# working.net
KiCad netlist of a schematic drawn in EAGLE
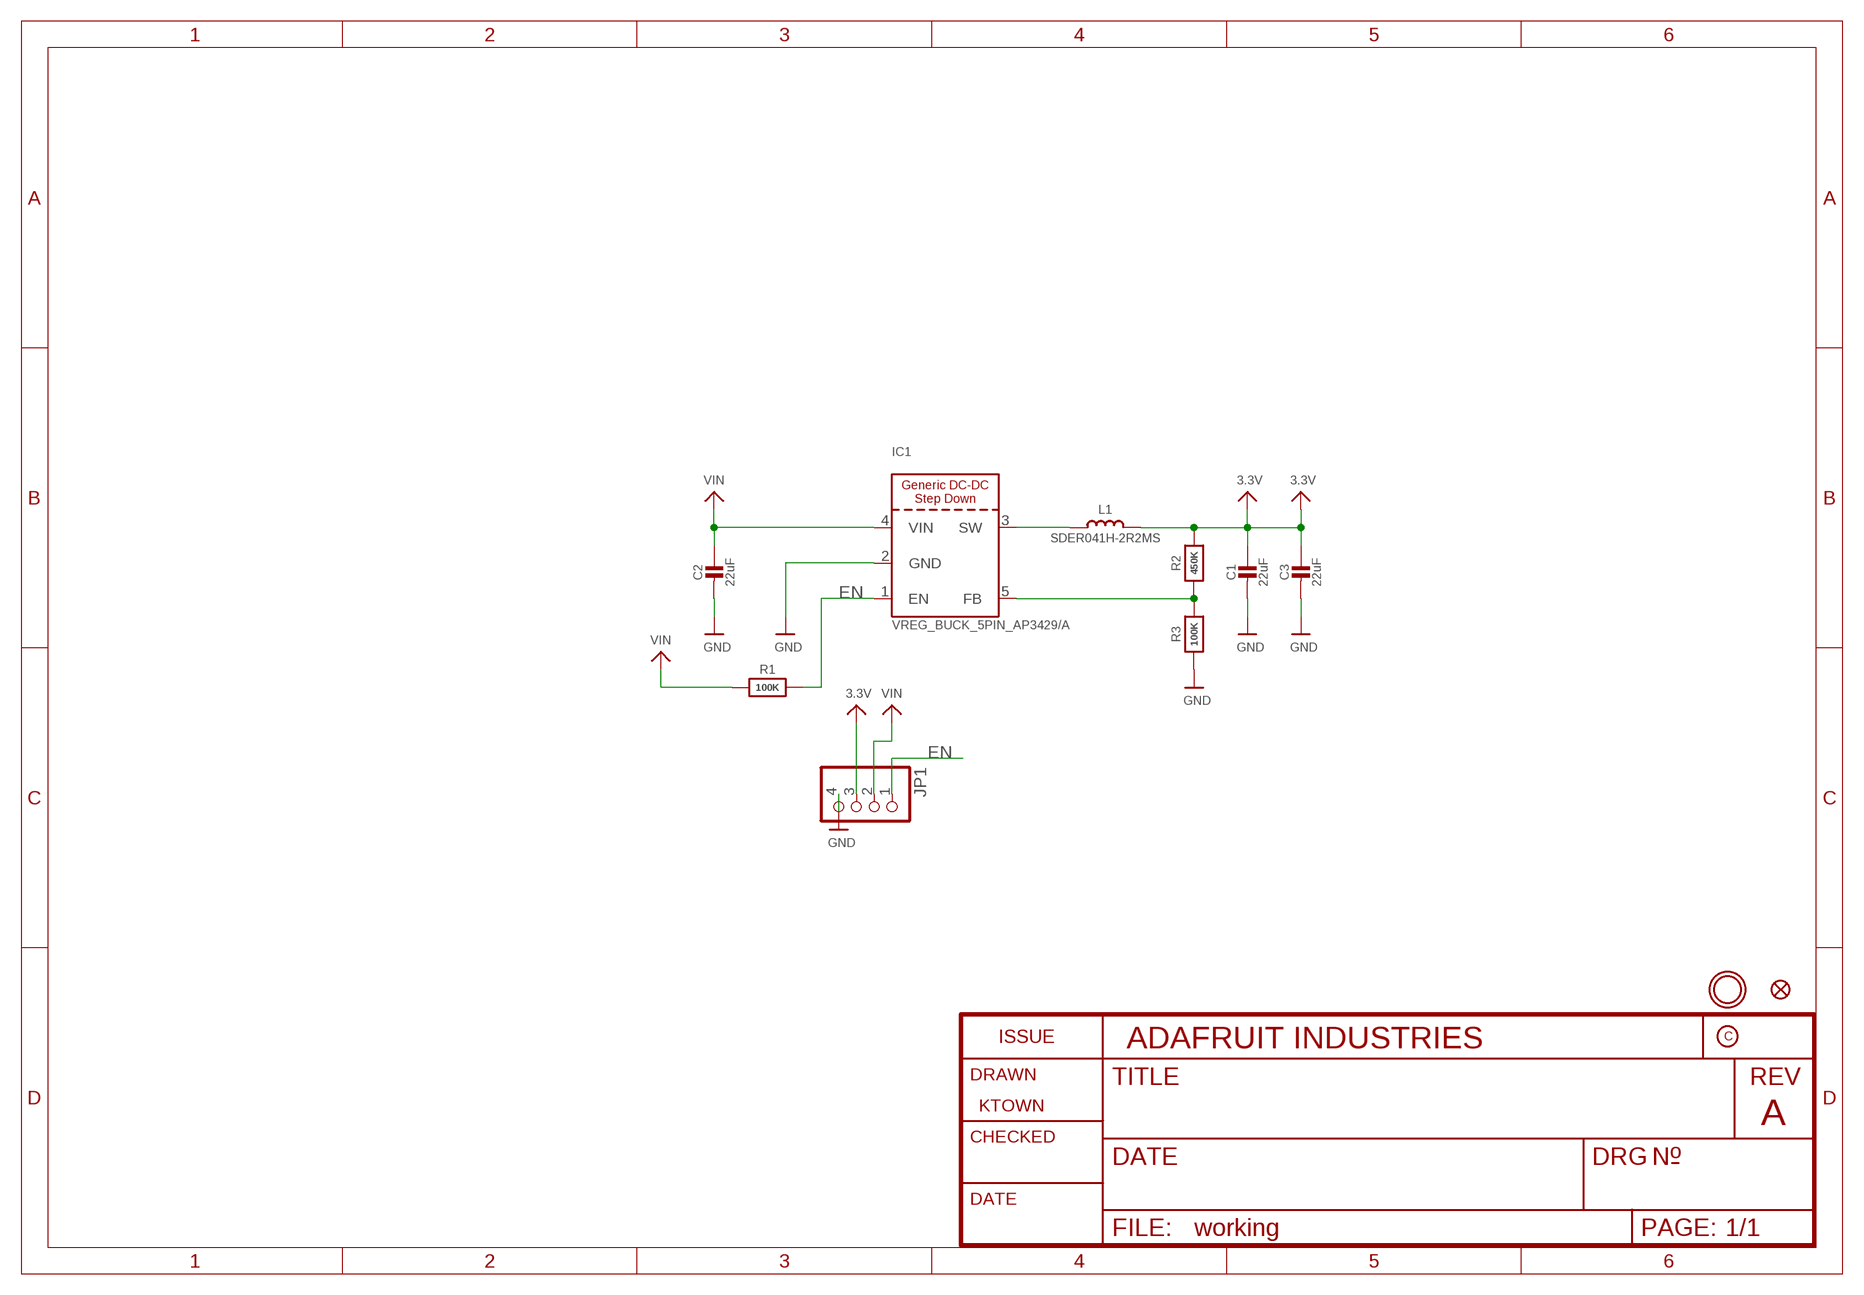
[diagram p0: schematic, sheet 1]

(export (version "E")
  (design (tool "Eeschema 10.0.6"))
  (components
    (comp (ref "C1")
      (value "22uF")
      (footprint "eagle-import:0805-NO")
      (libsource (lib "eagle-import") (part "CAP_CERAMIC0805-NOOUTLINE"))
    )
    (comp (ref "C2")
      (value "22uF")
      (footprint "eagle-import:0805-NO")
      (libsource (lib "eagle-import") (part "CAP_CERAMIC0805-NOOUTLINE"))
    )
    (comp (ref "C3")
      (value "22uF")
      (footprint "eagle-import:0805-NO")
      (libsource (lib "eagle-import") (part "CAP_CERAMIC0805-NOOUTLINE"))
    )
    (comp (ref "FID1")
      (value "FIDUCIAL_1MM")
      (footprint "eagle-import:FIDUCIAL_1MM")
      (libsource (lib "eagle-import") (part "FIDUCIAL_1MM"))
    )
    (comp (ref "IC1")
      (value "VREG_BUCK_5PIN_AP3429/A")
      (footprint "eagle-import:SOT23-5")
      (libsource (lib "eagle-import") (part "VREG_BUCK_5PIN_AP3429/A"))
    )
    (comp (ref "JP1")
      (value "HEADER-1X4ROUND")
      (footprint "eagle-import:1X04_ROUND")
      (libsource (lib "eagle-import") (part "HEADER-1X4ROUND"))
    )
    (comp (ref "L1")
      (value "SDER041H-2R2MS")
      (footprint "eagle-import:INDUCTOR_TAIYOYUDEN_NRH2412T")
      (libsource (lib "eagle-import") (part "INDUCTORNRH2412T"))
    )
    (comp (ref "R1")
      (value "100K")
      (footprint "eagle-import:0603-NO")
      (libsource (lib "eagle-import") (part "RESISTOR_0603_NOOUT"))
    )
    (comp (ref "R2")
      (value "450K")
      (footprint "eagle-import:0603-NO")
      (libsource (lib "eagle-import") (part "RESISTOR_0603_NOOUT"))
    )
    (comp (ref "R3")
      (value "100K")
      (footprint "eagle-import:0603-NO")
      (libsource (lib "eagle-import") (part "RESISTOR_0603_NOOUT"))
    )
    (comp (ref "U$9")
      (value "MOUNTINGHOLE2.5")
      (footprint "eagle-import:MOUNTINGHOLE_2.5_PLATED")
      (libsource (lib "eagle-import") (part "MOUNTINGHOLE2.5"))
    )
  )
  (nets
    (net (code "1") (name "/EN") (class "Default")
      (node (ref "IC1") (pin "1") (pinfunction "EN_1") (pintype "input"))
      (node (ref "JP1") (pin "1") (pinfunction "1_1") (pintype "passive"))
      (node (ref "R1") (pin "2") (pinfunction "2_2") (pintype "passive"))
    )
    (net (code "2") (name "3.3V") (class "Default")
      (node (ref "C1") (pin "1") (pinfunction "1_1") (pintype "passive"))
      (node (ref "C3") (pin "1") (pinfunction "1_1") (pintype "passive"))
      (node (ref "JP1") (pin "3") (pinfunction "3_3") (pintype "passive"))
      (node (ref "L1") (pin "2") (pinfunction "2_2") (pintype "passive"))
      (node (ref "R2") (pin "2") (pinfunction "2_2") (pintype "passive"))
    )
    (net (code "3") (name "GND") (class "Default")
      (node (ref "C1") (pin "2") (pinfunction "2_2") (pintype "passive"))
      (node (ref "C2") (pin "2") (pinfunction "2_2") (pintype "passive"))
      (node (ref "C3") (pin "2") (pinfunction "2_2") (pintype "passive"))
      (node (ref "IC1") (pin "2") (pinfunction "GND_2") (pintype "power_in"))
      (node (ref "JP1") (pin "4") (pinfunction "4_4") (pintype "passive"))
      (node (ref "R3") (pin "1") (pinfunction "1_1") (pintype "passive"))
    )
    (net (code "4") (name "Net-(IC1-FB)") (class "Default")
      (node (ref "IC1") (pin "5") (pinfunction "FB_5") (pintype "power_in"))
      (node (ref "R2") (pin "1") (pinfunction "1_1") (pintype "passive"))
      (node (ref "R3") (pin "2") (pinfunction "2_2") (pintype "passive"))
    )
    (net (code "5") (name "Net-(IC1-SW)") (class "Default")
      (node (ref "IC1") (pin "3") (pinfunction "SW_3") (pintype "output"))
      (node (ref "L1") (pin "1") (pinfunction "1_1") (pintype "passive"))
    )
    (net (code "6") (name "VIN") (class "Default")
      (node (ref "C2") (pin "1") (pinfunction "1_1") (pintype "passive"))
      (node (ref "IC1") (pin "4") (pinfunction "VIN_4") (pintype "power_in"))
      (node (ref "JP1") (pin "2") (pinfunction "2_2") (pintype "passive"))
      (node (ref "R1") (pin "1") (pinfunction "1_1") (pintype "passive"))
    )
  )
)
